# MHM01.net
KiCad netlist of a schematic drawn in EAGLE
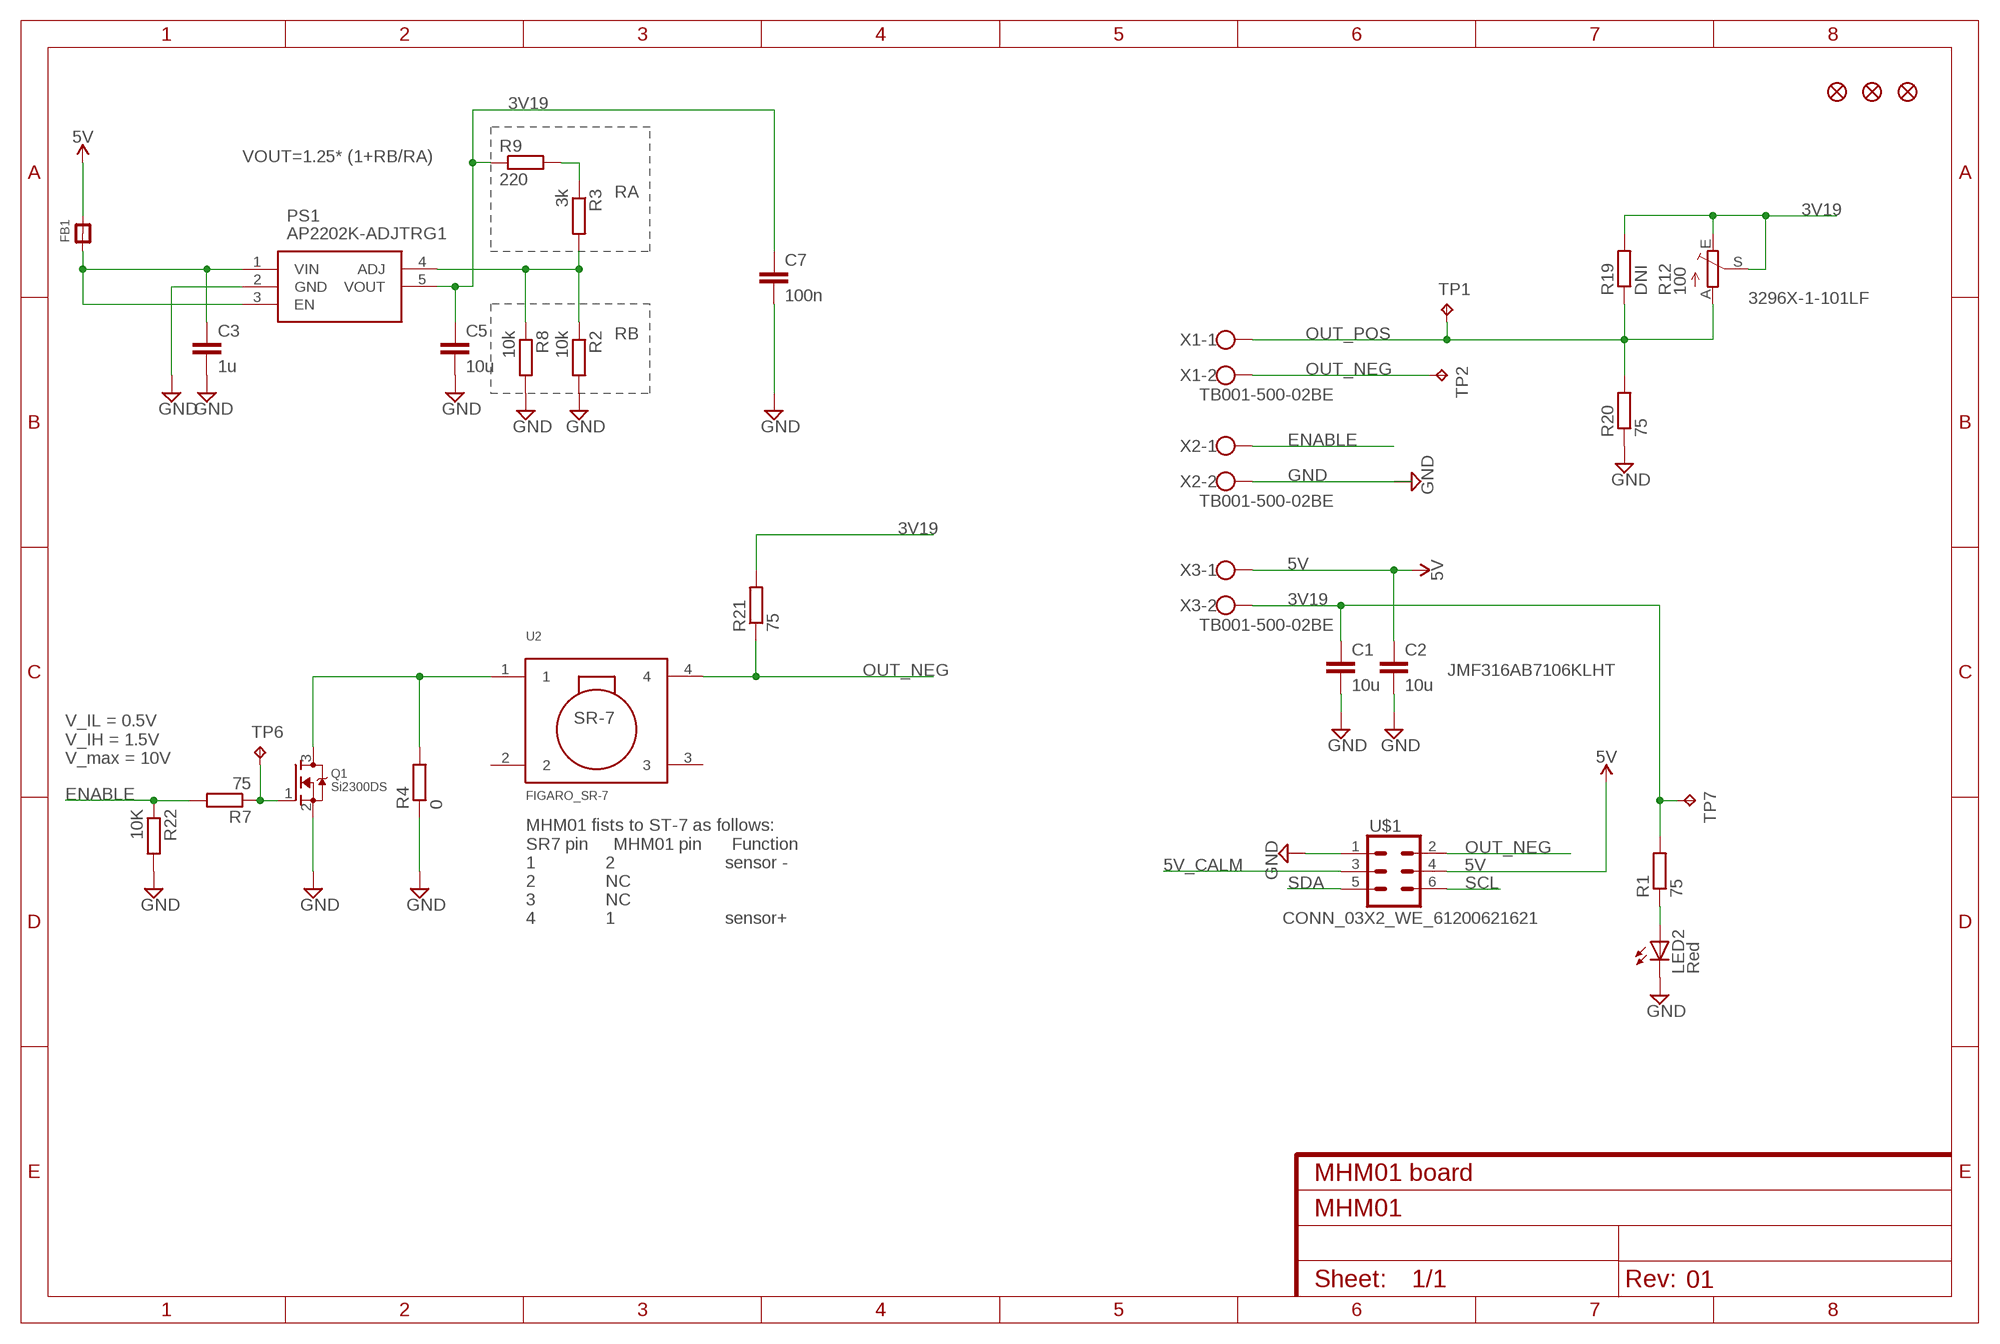
[diagram p0: schematic, sheet 1]

(export (version "E")
  (design (tool "Eeschema 10.0.6"))
  (components
    (comp (ref "C1")
      (value "10u")
      (footprint "eagle-import:C1206")
      (fields (field (name "PARTNO") "JMF316AB7106KLHT"))
      (libsource (lib "eagle-import") (part "C-EUC1206"))
    )
    (comp (ref "C2")
      (value "10u")
      (footprint "eagle-import:C1206")
      (fields (field (name "PARTNO") "JMF316AB7106KLHT"))
      (libsource (lib "eagle-import") (part "C-EUC1206"))
    )
    (comp (ref "C3")
      (value "1u")
      (footprint "eagle-import:C0603K")
      (fields (field (name "PARTNO") "GRM188R71C105KE15D"))
      (libsource (lib "eagle-import") (part "resistor_C-EUC0603K"))
    )
    (comp (ref "C5")
      (value "10u")
      (footprint "eagle-import:C0603K")
      (fields (field (name "PARTNO") "GRM188R61A106KE69J"))
      (libsource (lib "eagle-import") (part "resistor_C-EUC0603K"))
    )
    (comp (ref "C7")
      (value "100n")
      (footprint "eagle-import:C0603K")
      (fields (field (name "PARTNO") "CC0603KRX7R8BB104"))
      (libsource (lib "eagle-import") (part "resistor_C-EUC0603K"))
    )
    (comp (ref "FB1")
      (value "FERRITE")
      (footprint "eagle-import:0603")
      (fields (field (name "PARTNO") "BLM18PG121SN1D"))
      (libsource (lib "eagle-import") (part "FERRITE"))
    )
    (comp (ref "FID1")
      (value "FIDUCIAL\"\"")
      (footprint "eagle-import:FIDUCIAL_1MM")
      (libsource (lib "eagle-import") (part "FIDUCIAL{dblquote}{dblquote}"))
    )
    (comp (ref "FID2")
      (value "FIDUCIAL\"\"")
      (footprint "eagle-import:FIDUCIAL_1MM")
      (libsource (lib "eagle-import") (part "FIDUCIAL{dblquote}{dblquote}"))
    )
    (comp (ref "FID4")
      (value "FIDUCIAL\"\"")
      (footprint "eagle-import:FIDUCIAL_1MM")
      (libsource (lib "eagle-import") (part "FIDUCIAL{dblquote}{dblquote}"))
    )
    (comp (ref "LED2")
      (value "Red")
      (footprint "eagle-import:CHIPLED_1206")
      (fields (field (name "PARTNO") "BR1101W-TR"))
      (libsource (lib "eagle-import") (part "LEDCHIPLED_1206"))
    )
    (comp (ref "PS1")
      (value "AP2202K-ADJTRG1")
      (footprint "eagle-import:SOT95P280X145-5N")
      (fields (field (name "MOUSER_PART_NUMBER") "621-AP2202K-ADJTRG1"))
      (libsource (lib "eagle-import") (part "AP2202K-ADJTRG1"))
    )
    (comp (ref "Q1")
      (value "Si2300DS")
      (footprint "eagle-import:SOT23")
      (fields (field (name "PARTNO") "JMF316AB7106KLHT"))
      (libsource (lib "eagle-import") (part "MOSFET-NREFLOW"))
    )
    (comp (ref "R1")
      (value "75")
      (footprint "eagle-import:R1206")
      (fields (field (name "PARTNO") "CRCW120675R0FKEA"))
      (libsource (lib "eagle-import") (part "R-EU_R1206"))
    )
    (comp (ref "R2")
      (value "10k")
      (footprint "eagle-import:R0603")
      (fields (field (name "PARTNO") "CRCW060310K0FKEA"))
      (libsource (lib "eagle-import") (part "resistor_R-EU_R0603"))
    )
    (comp (ref "R3")
      (value "3k")
      (footprint "eagle-import:R0603")
      (fields (field (name "PARTNO") "ERA-3AEB302V"))
      (libsource (lib "eagle-import") (part "resistor_R-EU_R0603"))
    )
    (comp (ref "R4")
      (value "0")
      (footprint "eagle-import:R1206")
      (fields (field (name "PARTNO") "CRCW12060000Z0EA"))
      (libsource (lib "eagle-import") (part "R-EU_R1206"))
    )
    (comp (ref "R7")
      (value "75")
      (footprint "eagle-import:R1206")
      (fields (field (name "PARTNO") "CRCW120675R0FKEA"))
      (libsource (lib "eagle-import") (part "R-EU_R1206"))
    )
    (comp (ref "R8")
      (value "10k")
      (footprint "eagle-import:R0603")
      (fields (field (name "PARTNO") "CRCW060310K0FKEA"))
      (libsource (lib "eagle-import") (part "resistor_R-EU_R0603"))
    )
    (comp (ref "R9")
      (value "220")
      (footprint "eagle-import:R0603")
      (fields (field (name "PARTNO") "CRCW0603220RFKEA"))
      (libsource (lib "eagle-import") (part "resistor_R-EU_R0603"))
    )
    (comp (ref "R12")
      (value "100")
      (footprint "eagle-import:RJ9W")
      (fields (field (name "PARTNO") "3296X-1-101LF"))
      (libsource (lib "eagle-import") (part "TRIM_EU-RJ9W"))
    )
    (comp (ref "R19")
      (value "DNI")
      (footprint "eagle-import:R1206")
      (libsource (lib "eagle-import") (part "R-EU_R1206"))
    )
    (comp (ref "R20")
      (value "75")
      (footprint "eagle-import:R1206")
      (fields (field (name "PARTNO") "CRCW120675R0FKEA"))
      (libsource (lib "eagle-import") (part "R-EU_R1206"))
    )
    (comp (ref "R21")
      (value "75")
      (footprint "eagle-import:R1206")
      (fields (field (name "PARTNO") "CRCW120675R0FKEA"))
      (libsource (lib "eagle-import") (part "R-EU_R1206"))
    )
    (comp (ref "R22")
      (value "10K")
      (footprint "eagle-import:R1206")
      (fields (field (name "PARTNO") "CRCW120610K0FKEA"))
      (libsource (lib "eagle-import") (part "R-EU_R1206"))
    )
    (comp (ref "TP1")
      (value "TPTP10R")
      (footprint "eagle-import:TP10R")
      (libsource (lib "eagle-import") (part "TPTP10R"))
    )
    (comp (ref "TP2")
      (value "TPTP10R")
      (footprint "eagle-import:TP10R")
      (libsource (lib "eagle-import") (part "TPTP10R"))
    )
    (comp (ref "TP6")
      (value "TPTP10R")
      (footprint "eagle-import:TP10R")
      (libsource (lib "eagle-import") (part "TPTP10R"))
    )
    (comp (ref "TP7")
      (value "TPTP10R")
      (footprint "eagle-import:TP10R")
      (libsource (lib "eagle-import") (part "TPTP10R"))
    )
    (comp (ref "U$1")
      (value "CONN_03X2_WE_61200621621")
      (footprint "eagle-import:WE_61200621621")
      (fields (field (name "PARTNO") "61200621621"))
      (libsource (lib "eagle-import") (part "CONN_03X2_WE_61200621621"))
    )
    (comp (ref "U2")
      (value "FIGARO_SR-7")
      (footprint "eagle-import:FIGARO-SR7")
      (fields (field (name "PARTNO") "SR-7"))
      (libsource (lib "eagle-import") (part "FIGARO_SR-7"))
    )
    (comp (ref "X1")
      (value "TB001-500-02BE")
      (footprint "eagle-import:W237-102")
      (fields (field (name "MPN") "237-102") (field (name "PARTNO") "TB001-500-02BE"))
      (libsource (lib "eagle-import") (part "W237-102"))
    )
    (comp (ref "X2")
      (value "TB001-500-02BE")
      (footprint "eagle-import:W237-102")
      (fields (field (name "MPN") "237-102") (field (name "PARTNO") "TB001-500-02BE"))
      (libsource (lib "eagle-import") (part "W237-102"))
    )
    (comp (ref "X3")
      (value "TB001-500-02BE")
      (footprint "eagle-import:W237-102")
      (fields (field (name "MPN") "237-102") (field (name "PARTNO") "TB001-500-02BE"))
      (libsource (lib "eagle-import") (part "W237-102"))
    )
  )
  (nets
    (net (code "1") (name "/3V19") (class "Default")
      (node (ref "C1") (pin "1") (pinfunction "1_1") (pintype "passive"))
      (node (ref "C5") (pin "1") (pinfunction "1_1") (pintype "passive"))
      (node (ref "C7") (pin "1") (pinfunction "1_1") (pintype "passive"))
      (node (ref "PS1") (pin "5") (pinfunction "VOUT_5") (pintype "power_in"))
      (node (ref "R1") (pin "2") (pinfunction "2_2") (pintype "passive"))
      (node (ref "R12") (pin "E") (pinfunction "E_E") (pintype "passive"))
      (node (ref "R12") (pin "S") (pinfunction "S_S") (pintype "passive"))
      (node (ref "R19") (pin "2") (pinfunction "2_2") (pintype "passive"))
      (node (ref "R21") (pin "2") (pinfunction "2_2") (pintype "passive"))
      (node (ref "R9") (pin "1") (pinfunction "1_1") (pintype "passive"))
      (node (ref "TP7") (pin "TP") (pinfunction "TP_TP") (pintype "input"))
      (node (ref "X3") (pin "2") (pinfunction "KL_2") (pintype "passive"))
    )
    (net (code "2") (name "/5V_CALM") (class "Default")
      (node (ref "U$1") (pin "3") (pinfunction "3_3") (pintype "bidirectional"))
    )
    (net (code "3") (name "/ENABLE") (class "Default")
      (node (ref "R22") (pin "1") (pinfunction "1_1") (pintype "passive"))
      (node (ref "R7") (pin "2") (pinfunction "2_2") (pintype "passive"))
      (node (ref "X2") (pin "1") (pinfunction "KL_1") (pintype "passive"))
    )
    (net (code "4") (name "/OUT_NEG") (class "Default")
      (node (ref "R21") (pin "1") (pinfunction "1_1") (pintype "passive"))
      (node (ref "TP2") (pin "TP") (pinfunction "TP_TP") (pintype "input"))
      (node (ref "U$1") (pin "2") (pinfunction "2_2") (pintype "bidirectional"))
      (node (ref "U2") (pin "4") (pinfunction "4_4") (pintype "bidirectional"))
      (node (ref "X1") (pin "2") (pinfunction "KL_2") (pintype "passive"))
    )
    (net (code "5") (name "/OUT_POS") (class "Default")
      (node (ref "R12") (pin "A") (pinfunction "A_A") (pintype "passive"))
      (node (ref "R19") (pin "1") (pinfunction "1_1") (pintype "passive"))
      (node (ref "R20") (pin "2") (pinfunction "2_2") (pintype "passive"))
      (node (ref "TP1") (pin "TP") (pinfunction "TP_TP") (pintype "input"))
      (node (ref "X1") (pin "1") (pinfunction "KL_1") (pintype "passive"))
    )
    (net (code "6") (name "/SCL") (class "Default")
      (node (ref "U$1") (pin "6") (pinfunction "6_6") (pintype "bidirectional"))
    )
    (net (code "7") (name "/SDA") (class "Default")
      (node (ref "U$1") (pin "5") (pinfunction "5_5") (pintype "bidirectional"))
    )
    (net (code "8") (name "5V") (class "Default")
      (node (ref "C2") (pin "1") (pinfunction "1_1") (pintype "passive"))
      (node (ref "FB1") (pin "2") (pinfunction "P$2_2") (pintype "passive"))
      (node (ref "U$1") (pin "4") (pinfunction "4_4") (pintype "bidirectional"))
      (node (ref "X3") (pin "1") (pinfunction "KL_1") (pintype "passive"))
    )
    (net (code "9") (name "GND") (class "Default")
      (node (ref "C1") (pin "2") (pinfunction "2_2") (pintype "passive"))
      (node (ref "C2") (pin "2") (pinfunction "2_2") (pintype "passive"))
      (node (ref "C3") (pin "2") (pinfunction "2_2") (pintype "passive"))
      (node (ref "C5") (pin "2") (pinfunction "2_2") (pintype "passive"))
      (node (ref "C7") (pin "2") (pinfunction "2_2") (pintype "passive"))
      (node (ref "LED2") (pin "C") (pinfunction "C_C") (pintype "passive"))
      (node (ref "PS1") (pin "2") (pinfunction "GND_2") (pintype "power_in"))
      (node (ref "Q1") (pin "2") (pinfunction "S_2") (pintype "bidirectional"))
      (node (ref "R2") (pin "2") (pinfunction "2_2") (pintype "passive"))
      (node (ref "R20") (pin "1") (pinfunction "1_1") (pintype "passive"))
      (node (ref "R22") (pin "2") (pinfunction "2_2") (pintype "passive"))
      (node (ref "R4") (pin "1") (pinfunction "1_1") (pintype "passive"))
      (node (ref "R8") (pin "2") (pinfunction "2_2") (pintype "passive"))
      (node (ref "U$1") (pin "1") (pinfunction "1_1") (pintype "bidirectional"))
      (node (ref "X2") (pin "2") (pinfunction "KL_2") (pintype "passive"))
    )
    (net (code "10") (name "Net-(FB1-P$1)") (class "Default")
      (node (ref "C3") (pin "1") (pinfunction "1_1") (pintype "passive"))
      (node (ref "FB1") (pin "1") (pinfunction "P$1_1") (pintype "passive"))
      (node (ref "PS1") (pin "1") (pinfunction "VIN_1") (pintype "power_in"))
      (node (ref "PS1") (pin "3") (pinfunction "EN_3") (pintype "input"))
    )
    (net (code "11") (name "Net-(LED2-PadA)") (class "Default")
      (node (ref "LED2") (pin "A") (pinfunction "A_A") (pintype "passive"))
      (node (ref "R1") (pin "1") (pinfunction "1_1") (pintype "passive"))
    )
    (net (code "12") (name "Net-(PS1-ADJ)") (class "Default")
      (node (ref "PS1") (pin "4") (pinfunction "ADJ_4") (pintype "bidirectional"))
      (node (ref "R2") (pin "1") (pinfunction "1_1") (pintype "passive"))
      (node (ref "R3") (pin "2") (pinfunction "2_2") (pintype "passive"))
      (node (ref "R8") (pin "1") (pinfunction "1_1") (pintype "passive"))
    )
    (net (code "13") (name "Net-(Q1-D)") (class "Default")
      (node (ref "Q1") (pin "3") (pinfunction "D_3") (pintype "bidirectional"))
      (node (ref "R4") (pin "2") (pinfunction "2_2") (pintype "passive"))
      (node (ref "U2") (pin "1") (pinfunction "1_1") (pintype "bidirectional"))
    )
    (net (code "14") (name "Net-(Q1-G)") (class "Default")
      (node (ref "Q1") (pin "1") (pinfunction "G_1") (pintype "bidirectional"))
      (node (ref "R7") (pin "1") (pinfunction "1_1") (pintype "passive"))
      (node (ref "TP6") (pin "TP") (pinfunction "TP_TP") (pintype "input"))
    )
    (net (code "15") (name "Net-(R3-Pad1)") (class "Default")
      (node (ref "R3") (pin "1") (pinfunction "1_1") (pintype "passive"))
      (node (ref "R9") (pin "2") (pinfunction "2_2") (pintype "passive"))
    )
    (net (code "16") (name "unconnected-(U2-Pad2)") (class "Default")
      (node (ref "U2") (pin "2") (pinfunction "2_2") (pintype "bidirectional"))
    )
    (net (code "17") (name "unconnected-(U2-Pad3)") (class "Default")
      (node (ref "U2") (pin "3") (pinfunction "3_3") (pintype "bidirectional"))
    )
  )
)
